# Adafruit_NeoPixel_8_Stick.net
KiCad netlist of a schematic drawn in EAGLE
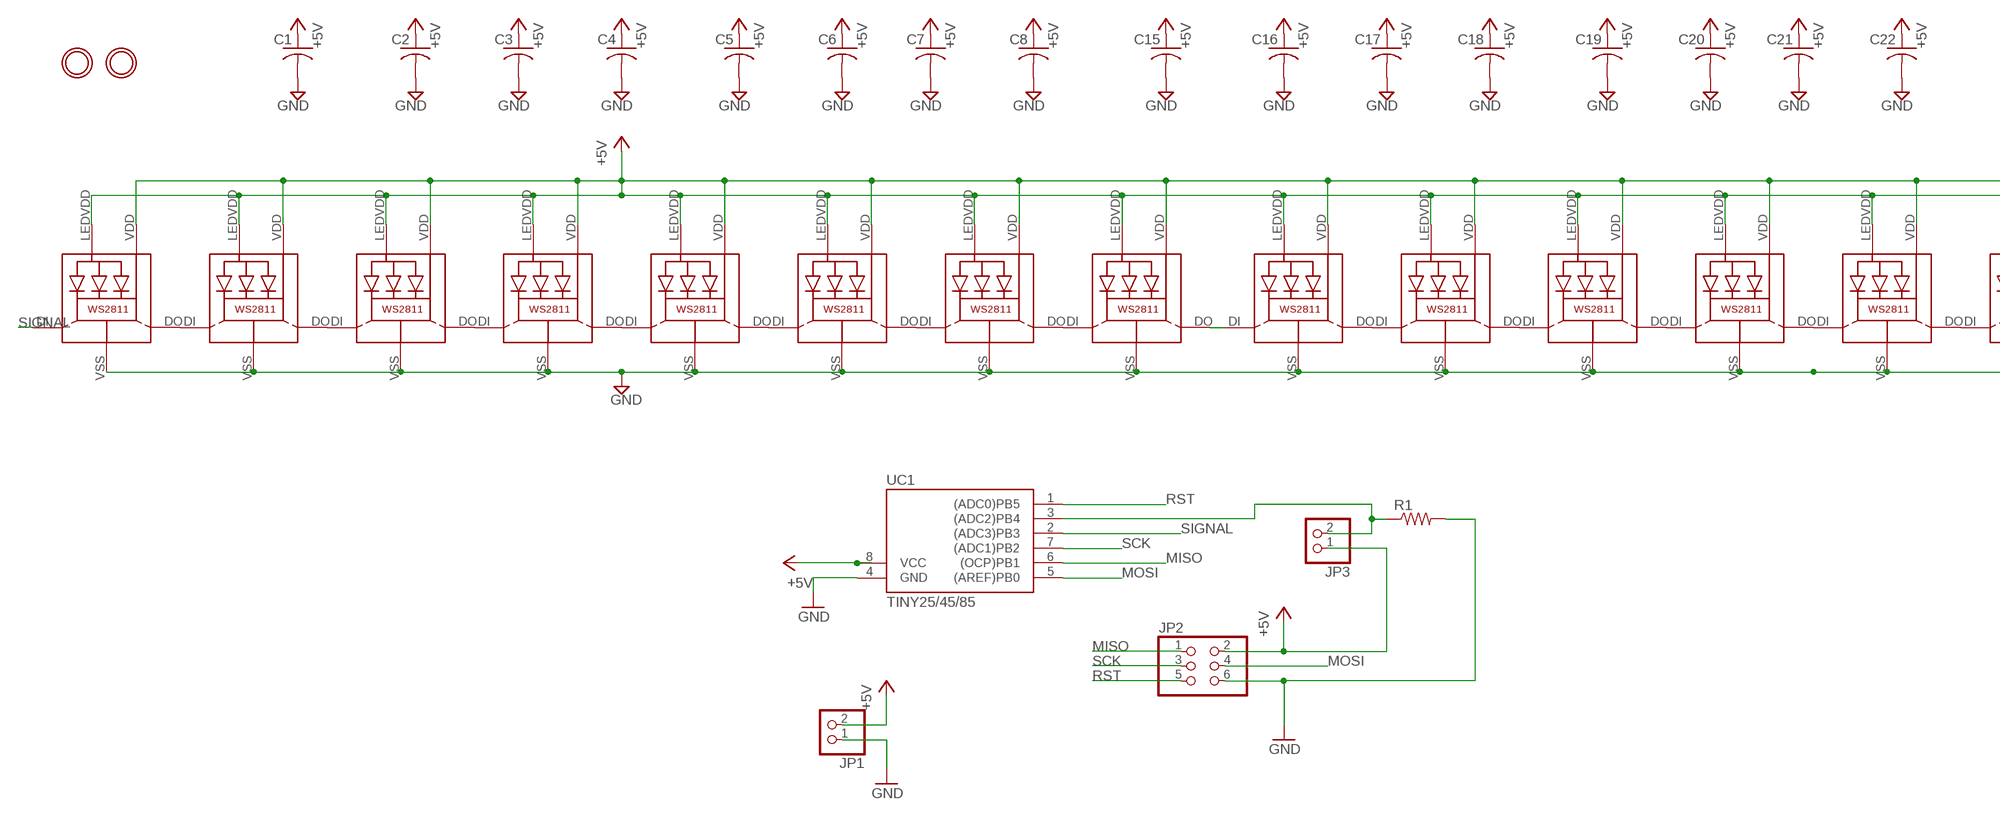
[diagram p0: schematic, sheet 1, part 1 of 2]
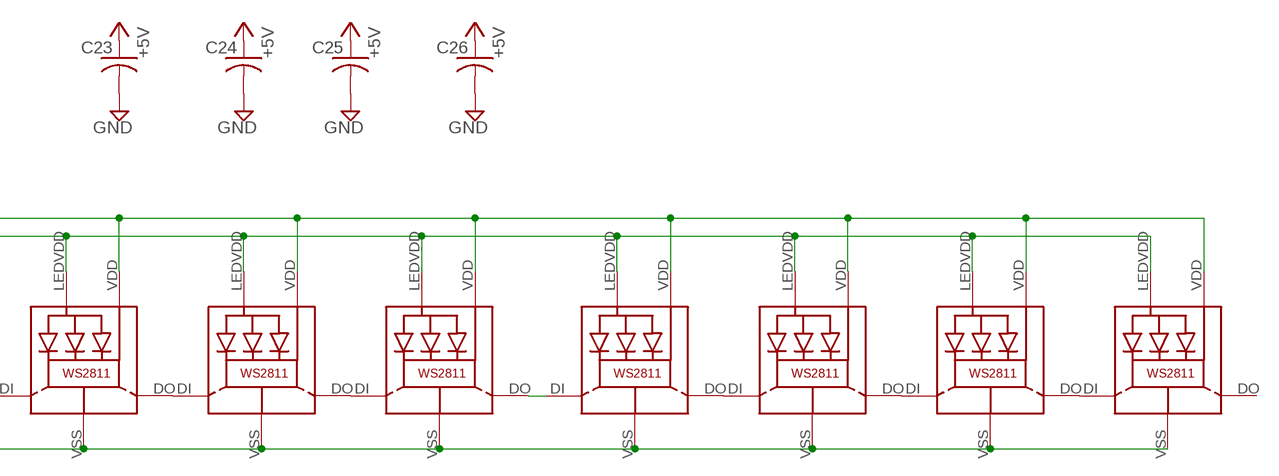
[diagram p1: schematic, sheet 1, part 2 of 2]

(export (version "E")
  (design (tool "Eeschema 10.0.6"))
  (components
    (comp (ref "C1")
      (value "C-USC0805K")
      (footprint "eagle-import:C0805K")
      (libsource (lib "eagle-import") (part "C-USC0805K"))
    )
    (comp (ref "C2")
      (value "C-USC0805K")
      (footprint "eagle-import:C0805K")
      (libsource (lib "eagle-import") (part "C-USC0805K"))
    )
    (comp (ref "C3")
      (value "C-USC0805K")
      (footprint "eagle-import:C0805K")
      (libsource (lib "eagle-import") (part "C-USC0805K"))
    )
    (comp (ref "C4")
      (value "C-USC0805K")
      (footprint "eagle-import:C0805K")
      (libsource (lib "eagle-import") (part "C-USC0805K"))
    )
    (comp (ref "C5")
      (value "C-USC0805K")
      (footprint "eagle-import:C0805K")
      (libsource (lib "eagle-import") (part "C-USC0805K"))
    )
    (comp (ref "C6")
      (value "C-USC0805K")
      (footprint "eagle-import:C0805K")
      (libsource (lib "eagle-import") (part "C-USC0805K"))
    )
    (comp (ref "C7")
      (value "C-USC0805K")
      (footprint "eagle-import:C0805K")
      (libsource (lib "eagle-import") (part "C-USC0805K"))
    )
    (comp (ref "C8")
      (value "C-USC0805K")
      (footprint "eagle-import:C0805K")
      (libsource (lib "eagle-import") (part "C-USC0805K"))
    )
    (comp (ref "C15")
      (value "C-USC0805K")
      (footprint "eagle-import:C0805K")
      (libsource (lib "eagle-import") (part "C-USC0805K"))
    )
    (comp (ref "C16")
      (value "C-USC0805K")
      (footprint "eagle-import:C0805K")
      (libsource (lib "eagle-import") (part "C-USC0805K"))
    )
    (comp (ref "C17")
      (value "C-USC0805K")
      (footprint "eagle-import:C0805K")
      (libsource (lib "eagle-import") (part "C-USC0805K"))
    )
    (comp (ref "C18")
      (value "C-USC0805K")
      (footprint "eagle-import:C0805K")
      (libsource (lib "eagle-import") (part "C-USC0805K"))
    )
    (comp (ref "C19")
      (value "C-USC0805K")
      (footprint "eagle-import:C0805K")
      (libsource (lib "eagle-import") (part "C-USC0805K"))
    )
    (comp (ref "C20")
      (value "C-USC0805K")
      (footprint "eagle-import:C0805K")
      (libsource (lib "eagle-import") (part "C-USC0805K"))
    )
    (comp (ref "C21")
      (value "C-USC0805K")
      (footprint "eagle-import:C0805K")
      (libsource (lib "eagle-import") (part "C-USC0805K"))
    )
    (comp (ref "C22")
      (value "C-USC0805K")
      (footprint "eagle-import:C0805K")
      (libsource (lib "eagle-import") (part "C-USC0805K"))
    )
    (comp (ref "C23")
      (value "C-USC0805K")
      (footprint "eagle-import:C0805K")
      (libsource (lib "eagle-import") (part "C-USC0805K"))
    )
    (comp (ref "C24")
      (value "C-USC0805K")
      (footprint "eagle-import:C0805K")
      (libsource (lib "eagle-import") (part "C-USC0805K"))
    )
    (comp (ref "C25")
      (value "C-USC0805K")
      (footprint "eagle-import:C0805K")
      (libsource (lib "eagle-import") (part "C-USC0805K"))
    )
    (comp (ref "C26")
      (value "C-USC0805K")
      (footprint "eagle-import:C0805K")
      (libsource (lib "eagle-import") (part "C-USC0805K"))
    )
    (comp (ref "JP1")
      (value "PINHD-1X02_2.54")
      (footprint "eagle-import:1X02")
      (libsource (lib "eagle-import") (part "PINHD-1X02_2.54"))
    )
    (comp (ref "JP2")
      (value "PINHD-2X03_2.54")
      (footprint "eagle-import:2X03")
      (libsource (lib "eagle-import") (part "PINHD-2X03_2.54"))
    )
    (comp (ref "JP3")
      (value "PINHD-1X02_2.54")
      (footprint "eagle-import:1X02")
      (libsource (lib "eagle-import") (part "PINHD-1X02_2.54"))
    )
    (comp (ref "LED1")
      (value "WS28115050")
      (footprint "eagle-import:WS28115050")
      (libsource (lib "eagle-import") (part "WS28115050"))
    )
    (comp (ref "LED2")
      (value "WS28115050")
      (footprint "eagle-import:WS28115050")
      (libsource (lib "eagle-import") (part "WS28115050"))
    )
    (comp (ref "LED3")
      (value "WS28115050")
      (footprint "eagle-import:WS28115050")
      (libsource (lib "eagle-import") (part "WS28115050"))
    )
    (comp (ref "LED4")
      (value "WS28115050")
      (footprint "eagle-import:WS28115050")
      (libsource (lib "eagle-import") (part "WS28115050"))
    )
    (comp (ref "LED5")
      (value "WS28115050")
      (footprint "eagle-import:WS28115050")
      (libsource (lib "eagle-import") (part "WS28115050"))
    )
    (comp (ref "LED6")
      (value "WS28115050")
      (footprint "eagle-import:WS28115050")
      (libsource (lib "eagle-import") (part "WS28115050"))
    )
    (comp (ref "LED7")
      (value "WS28115050")
      (footprint "eagle-import:WS28115050")
      (libsource (lib "eagle-import") (part "WS28115050"))
    )
    (comp (ref "LED8")
      (value "WS28115050")
      (footprint "eagle-import:WS28115050")
      (libsource (lib "eagle-import") (part "WS28115050"))
    )
    (comp (ref "LED11")
      (value "WS28115050")
      (footprint "eagle-import:WS28115050")
      (libsource (lib "eagle-import") (part "WS28115050"))
    )
    (comp (ref "LED12")
      (value "WS28115050")
      (footprint "eagle-import:WS28115050")
      (libsource (lib "eagle-import") (part "WS28115050"))
    )
    (comp (ref "LED13")
      (value "WS28115050")
      (footprint "eagle-import:WS28115050")
      (libsource (lib "eagle-import") (part "WS28115050"))
    )
    (comp (ref "LED14")
      (value "WS28115050")
      (footprint "eagle-import:WS28115050")
      (libsource (lib "eagle-import") (part "WS28115050"))
    )
    (comp (ref "LED15")
      (value "WS28115050")
      (footprint "eagle-import:WS28115050")
      (libsource (lib "eagle-import") (part "WS28115050"))
    )
    (comp (ref "LED16")
      (value "WS28115050")
      (footprint "eagle-import:WS28115050")
      (libsource (lib "eagle-import") (part "WS28115050"))
    )
    (comp (ref "LED17")
      (value "WS28115050")
      (footprint "eagle-import:WS28115050")
      (libsource (lib "eagle-import") (part "WS28115050"))
    )
    (comp (ref "LED18")
      (value "WS28115050")
      (footprint "eagle-import:WS28115050")
      (libsource (lib "eagle-import") (part "WS28115050"))
    )
    (comp (ref "LED19")
      (value "WS28115050")
      (footprint "eagle-import:WS28115050")
      (libsource (lib "eagle-import") (part "WS28115050"))
    )
    (comp (ref "LED20")
      (value "WS28115050")
      (footprint "eagle-import:WS28115050")
      (libsource (lib "eagle-import") (part "WS28115050"))
    )
    (comp (ref "LED21")
      (value "WS28115050")
      (footprint "eagle-import:WS28115050")
      (libsource (lib "eagle-import") (part "WS28115050"))
    )
    (comp (ref "LED22")
      (value "WS28115050")
      (footprint "eagle-import:WS28115050")
      (libsource (lib "eagle-import") (part "WS28115050"))
    )
    (comp (ref "R1")
      (value "R-US_M0805")
      (footprint "eagle-import:M0805")
      (libsource (lib "eagle-import") (part "R-US_M0805"))
    )
    (comp (ref "U$2")
      (value "MOUNTINGHOLE2.0")
      (footprint "eagle-import:MOUNTINGHOLE_2.0_PLATED")
      (libsource (lib "eagle-import") (part "MOUNTINGHOLE2.0"))
    )
    (comp (ref "U$3")
      (value "MOUNTINGHOLE2.0")
      (footprint "eagle-import:MOUNTINGHOLE_2.0_PLATED")
      (libsource (lib "eagle-import") (part "MOUNTINGHOLE2.0"))
    )
    (comp (ref "UC1")
      (value "TINY25/45/85")
      (footprint "eagle-import:SOIC8")
      (libsource (lib "eagle-import") (part "TINY25-20SU"))
    )
  )
  (nets
    (net (code "1") (name "+5V") (class "Default")
      (node (ref "C1") (pin "1") (pinfunction "1_1") (pintype "passive"))
      (node (ref "C15") (pin "1") (pinfunction "1_1") (pintype "passive"))
      (node (ref "C16") (pin "1") (pinfunction "1_1") (pintype "passive"))
      (node (ref "C17") (pin "1") (pinfunction "1_1") (pintype "passive"))
      (node (ref "C18") (pin "1") (pinfunction "1_1") (pintype "passive"))
      (node (ref "C19") (pin "1") (pinfunction "1_1") (pintype "passive"))
      (node (ref "C2") (pin "1") (pinfunction "1_1") (pintype "passive"))
      (node (ref "C20") (pin "1") (pinfunction "1_1") (pintype "passive"))
      (node (ref "C21") (pin "1") (pinfunction "1_1") (pintype "passive"))
      (node (ref "C22") (pin "1") (pinfunction "1_1") (pintype "passive"))
      (node (ref "C23") (pin "1") (pinfunction "1_1") (pintype "passive"))
      (node (ref "C24") (pin "1") (pinfunction "1_1") (pintype "passive"))
      (node (ref "C25") (pin "1") (pinfunction "1_1") (pintype "passive"))
      (node (ref "C26") (pin "1") (pinfunction "1_1") (pintype "passive"))
      (node (ref "C3") (pin "1") (pinfunction "1_1") (pintype "passive"))
      (node (ref "C4") (pin "1") (pinfunction "1_1") (pintype "passive"))
      (node (ref "C5") (pin "1") (pinfunction "1_1") (pintype "passive"))
      (node (ref "C6") (pin "1") (pinfunction "1_1") (pintype "passive"))
      (node (ref "C7") (pin "1") (pinfunction "1_1") (pintype "passive"))
      (node (ref "C8") (pin "1") (pinfunction "1_1") (pintype "passive"))
      (node (ref "JP1") (pin "2") (pinfunction "2_2") (pintype "passive"))
      (node (ref "JP2") (pin "2") (pinfunction "2_2") (pintype "passive"))
      (node (ref "JP3") (pin "1") (pinfunction "1_1") (pintype "passive"))
      (node (ref "LED1") (pin "LEDVDD") (pinfunction "LEDVDD_LEDVDD") (pintype "power_in"))
      (node (ref "LED1") (pin "VDD") (pinfunction "VDD_VDD") (pintype "power_in"))
      (node (ref "LED11") (pin "LEDVDD") (pinfunction "LEDVDD_LEDVDD") (pintype "power_in"))
      (node (ref "LED11") (pin "VDD") (pinfunction "VDD_VDD") (pintype "power_in"))
      (node (ref "LED12") (pin "LEDVDD") (pinfunction "LEDVDD_LEDVDD") (pintype "power_in"))
      (node (ref "LED12") (pin "VDD") (pinfunction "VDD_VDD") (pintype "power_in"))
      (node (ref "LED13") (pin "LEDVDD") (pinfunction "LEDVDD_LEDVDD") (pintype "power_in"))
      (node (ref "LED13") (pin "VDD") (pinfunction "VDD_VDD") (pintype "power_in"))
      (node (ref "LED14") (pin "LEDVDD") (pinfunction "LEDVDD_LEDVDD") (pintype "power_in"))
      (node (ref "LED14") (pin "VDD") (pinfunction "VDD_VDD") (pintype "power_in"))
      (node (ref "LED15") (pin "LEDVDD") (pinfunction "LEDVDD_LEDVDD") (pintype "power_in"))
      (node (ref "LED15") (pin "VDD") (pinfunction "VDD_VDD") (pintype "power_in"))
      (node (ref "LED16") (pin "LEDVDD") (pinfunction "LEDVDD_LEDVDD") (pintype "power_in"))
      (node (ref "LED16") (pin "VDD") (pinfunction "VDD_VDD") (pintype "power_in"))
      (node (ref "LED17") (pin "LEDVDD") (pinfunction "LEDVDD_LEDVDD") (pintype "power_in"))
      (node (ref "LED17") (pin "VDD") (pinfunction "VDD_VDD") (pintype "power_in"))
      (node (ref "LED18") (pin "LEDVDD") (pinfunction "LEDVDD_LEDVDD") (pintype "power_in"))
      (node (ref "LED18") (pin "VDD") (pinfunction "VDD_VDD") (pintype "power_in"))
      (node (ref "LED19") (pin "LEDVDD") (pinfunction "LEDVDD_LEDVDD") (pintype "power_in"))
      (node (ref "LED19") (pin "VDD") (pinfunction "VDD_VDD") (pintype "power_in"))
      (node (ref "LED2") (pin "LEDVDD") (pinfunction "LEDVDD_LEDVDD") (pintype "power_in"))
      (node (ref "LED2") (pin "VDD") (pinfunction "VDD_VDD") (pintype "power_in"))
      (node (ref "LED20") (pin "LEDVDD") (pinfunction "LEDVDD_LEDVDD") (pintype "power_in"))
      (node (ref "LED20") (pin "VDD") (pinfunction "VDD_VDD") (pintype "power_in"))
      (node (ref "LED21") (pin "LEDVDD") (pinfunction "LEDVDD_LEDVDD") (pintype "power_in"))
      (node (ref "LED21") (pin "VDD") (pinfunction "VDD_VDD") (pintype "power_in"))
      (node (ref "LED22") (pin "LEDVDD") (pinfunction "LEDVDD_LEDVDD") (pintype "power_in"))
      (node (ref "LED22") (pin "VDD") (pinfunction "VDD_VDD") (pintype "power_in"))
      (node (ref "LED3") (pin "LEDVDD") (pinfunction "LEDVDD_LEDVDD") (pintype "power_in"))
      (node (ref "LED3") (pin "VDD") (pinfunction "VDD_VDD") (pintype "power_in"))
      (node (ref "LED4") (pin "LEDVDD") (pinfunction "LEDVDD_LEDVDD") (pintype "power_in"))
      (node (ref "LED4") (pin "VDD") (pinfunction "VDD_VDD") (pintype "power_in"))
      (node (ref "LED5") (pin "LEDVDD") (pinfunction "LEDVDD_LEDVDD") (pintype "power_in"))
      (node (ref "LED5") (pin "VDD") (pinfunction "VDD_VDD") (pintype "power_in"))
      (node (ref "LED6") (pin "LEDVDD") (pinfunction "LEDVDD_LEDVDD") (pintype "power_in"))
      (node (ref "LED6") (pin "VDD") (pinfunction "VDD_VDD") (pintype "power_in"))
      (node (ref "LED7") (pin "LEDVDD") (pinfunction "LEDVDD_LEDVDD") (pintype "power_in"))
      (node (ref "LED7") (pin "VDD") (pinfunction "VDD_VDD") (pintype "power_in"))
      (node (ref "LED8") (pin "LEDVDD") (pinfunction "LEDVDD_LEDVDD") (pintype "power_in"))
      (node (ref "LED8") (pin "VDD") (pinfunction "VDD_VDD") (pintype "power_in"))
      (node (ref "UC1") (pin "8") (pinfunction "VCC_8") (pintype "power_in"))
    )
    (net (code "2") (name "/MISO") (class "Default")
      (node (ref "JP2") (pin "1") (pinfunction "1_1") (pintype "passive"))
      (node (ref "UC1") (pin "6") (pinfunction "(OCP)PB1_6") (pintype "bidirectional"))
    )
    (net (code "3") (name "/MOSI") (class "Default")
      (node (ref "JP2") (pin "4") (pinfunction "4_4") (pintype "passive"))
      (node (ref "UC1") (pin "5") (pinfunction "(AREF)PB0_5") (pintype "bidirectional"))
    )
    (net (code "4") (name "/RST") (class "Default")
      (node (ref "JP2") (pin "5") (pinfunction "5_5") (pintype "passive"))
      (node (ref "UC1") (pin "1") (pinfunction "(ADC0)PB5_1") (pintype "bidirectional"))
    )
    (net (code "5") (name "/SCK") (class "Default")
      (node (ref "JP2") (pin "3") (pinfunction "3_3") (pintype "passive"))
      (node (ref "UC1") (pin "7") (pinfunction "(ADC1)PB2_7") (pintype "bidirectional"))
    )
    (net (code "6") (name "/SIGNAL") (class "Default")
      (node (ref "LED1") (pin "DI") (pinfunction "DI_DI") (pintype "input"))
      (node (ref "UC1") (pin "2") (pinfunction "(ADC3)PB3_2") (pintype "bidirectional"))
    )
    (net (code "7") (name "GND") (class "Default")
      (node (ref "C1") (pin "2") (pinfunction "2_2") (pintype "passive"))
      (node (ref "C15") (pin "2") (pinfunction "2_2") (pintype "passive"))
      (node (ref "C16") (pin "2") (pinfunction "2_2") (pintype "passive"))
      (node (ref "C17") (pin "2") (pinfunction "2_2") (pintype "passive"))
      (node (ref "C18") (pin "2") (pinfunction "2_2") (pintype "passive"))
      (node (ref "C19") (pin "2") (pinfunction "2_2") (pintype "passive"))
      (node (ref "C2") (pin "2") (pinfunction "2_2") (pintype "passive"))
      (node (ref "C20") (pin "2") (pinfunction "2_2") (pintype "passive"))
      (node (ref "C21") (pin "2") (pinfunction "2_2") (pintype "passive"))
      (node (ref "C22") (pin "2") (pinfunction "2_2") (pintype "passive"))
      (node (ref "C23") (pin "2") (pinfunction "2_2") (pintype "passive"))
      (node (ref "C24") (pin "2") (pinfunction "2_2") (pintype "passive"))
      (node (ref "C25") (pin "2") (pinfunction "2_2") (pintype "passive"))
      (node (ref "C26") (pin "2") (pinfunction "2_2") (pintype "passive"))
      (node (ref "C3") (pin "2") (pinfunction "2_2") (pintype "passive"))
      (node (ref "C4") (pin "2") (pinfunction "2_2") (pintype "passive"))
      (node (ref "C5") (pin "2") (pinfunction "2_2") (pintype "passive"))
      (node (ref "C6") (pin "2") (pinfunction "2_2") (pintype "passive"))
      (node (ref "C7") (pin "2") (pinfunction "2_2") (pintype "passive"))
      (node (ref "C8") (pin "2") (pinfunction "2_2") (pintype "passive"))
      (node (ref "JP1") (pin "1") (pinfunction "1_1") (pintype "passive"))
      (node (ref "JP2") (pin "6") (pinfunction "6_6") (pintype "passive"))
      (node (ref "LED1") (pin "VSS") (pinfunction "GND_VSS") (pintype "power_in"))
      (node (ref "LED11") (pin "VSS") (pinfunction "GND_VSS") (pintype "power_in"))
      (node (ref "LED12") (pin "VSS") (pinfunction "GND_VSS") (pintype "power_in"))
      (node (ref "LED13") (pin "VSS") (pinfunction "GND_VSS") (pintype "power_in"))
      (node (ref "LED14") (pin "VSS") (pinfunction "GND_VSS") (pintype "power_in"))
      (node (ref "LED15") (pin "VSS") (pinfunction "GND_VSS") (pintype "power_in"))
      (node (ref "LED16") (pin "VSS") (pinfunction "GND_VSS") (pintype "power_in"))
      (node (ref "LED17") (pin "VSS") (pinfunction "GND_VSS") (pintype "power_in"))
      (node (ref "LED18") (pin "VSS") (pinfunction "GND_VSS") (pintype "power_in"))
      (node (ref "LED19") (pin "VSS") (pinfunction "GND_VSS") (pintype "power_in"))
      (node (ref "LED2") (pin "VSS") (pinfunction "GND_VSS") (pintype "power_in"))
      (node (ref "LED20") (pin "VSS") (pinfunction "GND_VSS") (pintype "power_in"))
      (node (ref "LED21") (pin "VSS") (pinfunction "GND_VSS") (pintype "power_in"))
      (node (ref "LED22") (pin "VSS") (pinfunction "GND_VSS") (pintype "power_in"))
      (node (ref "LED3") (pin "VSS") (pinfunction "GND_VSS") (pintype "power_in"))
      (node (ref "LED4") (pin "VSS") (pinfunction "GND_VSS") (pintype "power_in"))
      (node (ref "LED5") (pin "VSS") (pinfunction "GND_VSS") (pintype "power_in"))
      (node (ref "LED6") (pin "VSS") (pinfunction "GND_VSS") (pintype "power_in"))
      (node (ref "LED7") (pin "VSS") (pinfunction "GND_VSS") (pintype "power_in"))
      (node (ref "LED8") (pin "VSS") (pinfunction "GND_VSS") (pintype "power_in"))
      (node (ref "R1") (pin "2") (pinfunction "2_2") (pintype "passive"))
      (node (ref "UC1") (pin "4") (pinfunction "GND_4") (pintype "power_in"))
    )
    (net (code "8") (name "Net-(LED1-PadDO)") (class "Default")
      (node (ref "LED1") (pin "DO") (pinfunction "DO_DO") (pintype "output"))
      (node (ref "LED2") (pin "DI") (pinfunction "DI_DI") (pintype "input"))
    )
    (net (code "9") (name "Net-(LED2-PadDO)") (class "Default")
      (node (ref "LED2") (pin "DO") (pinfunction "DO_DO") (pintype "output"))
      (node (ref "LED3") (pin "DI") (pinfunction "DI_DI") (pintype "input"))
    )
    (net (code "10") (name "Net-(LED3-PadDO)") (class "Default")
      (node (ref "LED3") (pin "DO") (pinfunction "DO_DO") (pintype "output"))
      (node (ref "LED4") (pin "DI") (pinfunction "DI_DI") (pintype "input"))
    )
    (net (code "11") (name "Net-(LED4-PadDO)") (class "Default")
      (node (ref "LED4") (pin "DO") (pinfunction "DO_DO") (pintype "output"))
      (node (ref "LED5") (pin "DI") (pinfunction "DI_DI") (pintype "input"))
    )
    (net (code "12") (name "Net-(LED5-PadDO)") (class "Default")
      (node (ref "LED5") (pin "DO") (pinfunction "DO_DO") (pintype "output"))
      (node (ref "LED6") (pin "DI") (pinfunction "DI_DI") (pintype "input"))
    )
    (net (code "13") (name "Net-(LED6-PadDO)") (class "Default")
      (node (ref "LED6") (pin "DO") (pinfunction "DO_DO") (pintype "output"))
      (node (ref "LED7") (pin "DI") (pinfunction "DI_DI") (pintype "input"))
    )
    (net (code "14") (name "Net-(LED7-PadDO)") (class "Default")
      (node (ref "LED7") (pin "DO") (pinfunction "DO_DO") (pintype "output"))
      (node (ref "LED8") (pin "DI") (pinfunction "DI_DI") (pintype "input"))
    )
    (net (code "15") (name "Net-(LED11-PadDI)") (class "Default")
      (node (ref "LED11") (pin "DI") (pinfunction "DI_DI") (pintype "input"))
      (node (ref "LED8") (pin "DO") (pinfunction "DO_DO") (pintype "output"))
    )
    (net (code "16") (name "Net-(LED11-PadDO)") (class "Default")
      (node (ref "LED11") (pin "DO") (pinfunction "DO_DO") (pintype "output"))
      (node (ref "LED12") (pin "DI") (pinfunction "DI_DI") (pintype "input"))
    )
    (net (code "17") (name "Net-(LED12-PadDO)") (class "Default")
      (node (ref "LED12") (pin "DO") (pinfunction "DO_DO") (pintype "output"))
      (node (ref "LED13") (pin "DI") (pinfunction "DI_DI") (pintype "input"))
    )
    (net (code "18") (name "Net-(LED13-PadDO)") (class "Default")
      (node (ref "LED13") (pin "DO") (pinfunction "DO_DO") (pintype "output"))
      (node (ref "LED14") (pin "DI") (pinfunction "DI_DI") (pintype "input"))
    )
    (net (code "19") (name "Net-(LED14-PadDO)") (class "Default")
      (node (ref "LED14") (pin "DO") (pinfunction "DO_DO") (pintype "output"))
      (node (ref "LED15") (pin "DI") (pinfunction "DI_DI") (pintype "input"))
    )
    (net (code "20") (name "Net-(LED15-PadDO)") (class "Default")
      (node (ref "LED15") (pin "DO") (pinfunction "DO_DO") (pintype "output"))
      (node (ref "LED16") (pin "DI") (pinfunction "DI_DI") (pintype "input"))
    )
    (net (code "21") (name "Net-(LED16-PadDO)") (class "Default")
      (node (ref "LED16") (pin "DO") (pinfunction "DO_DO") (pintype "output"))
      (node (ref "LED17") (pin "DI") (pinfunction "DI_DI") (pintype "input"))
    )
    (net (code "22") (name "Net-(LED17-PadDO)") (class "Default")
      (node (ref "LED17") (pin "DO") (pinfunction "DO_DO") (pintype "output"))
      (node (ref "LED18") (pin "DI") (pinfunction "DI_DI") (pintype "input"))
    )
    (net (code "23") (name "Net-(LED18-PadDO)") (class "Default")
      (node (ref "LED18") (pin "DO") (pinfunction "DO_DO") (pintype "output"))
      (node (ref "LED19") (pin "DI") (pinfunction "DI_DI") (pintype "input"))
    )
    (net (code "24") (name "Net-(LED19-PadDO)") (class "Default")
      (node (ref "LED19") (pin "DO") (pinfunction "DO_DO") (pintype "output"))
      (node (ref "LED20") (pin "DI") (pinfunction "DI_DI") (pintype "input"))
    )
    (net (code "25") (name "Net-(LED20-PadDO)") (class "Default")
      (node (ref "LED20") (pin "DO") (pinfunction "DO_DO") (pintype "output"))
      (node (ref "LED21") (pin "DI") (pinfunction "DI_DI") (pintype "input"))
    )
    (net (code "26") (name "Net-(LED21-PadDO)") (class "Default")
      (node (ref "LED21") (pin "DO") (pinfunction "DO_DO") (pintype "output"))
      (node (ref "LED22") (pin "DI") (pinfunction "DI_DI") (pintype "input"))
    )
    (net (code "27") (name "Net-(UC1-(ADC2)PB4)") (class "Default")
      (node (ref "JP3") (pin "2") (pinfunction "2_2") (pintype "passive"))
      (node (ref "R1") (pin "1") (pinfunction "1_1") (pintype "passive"))
      (node (ref "UC1") (pin "3") (pinfunction "(ADC2)PB4_3") (pintype "bidirectional"))
    )
    (net (code "28") (name "unconnected-(LED22-PadDO)") (class "Default")
      (node (ref "LED22") (pin "DO") (pinfunction "DO_DO") (pintype "output"))
    )
  )
)
